# Booster_Board_20180904.net
KiCad netlist of a schematic drawn in Altium Designer
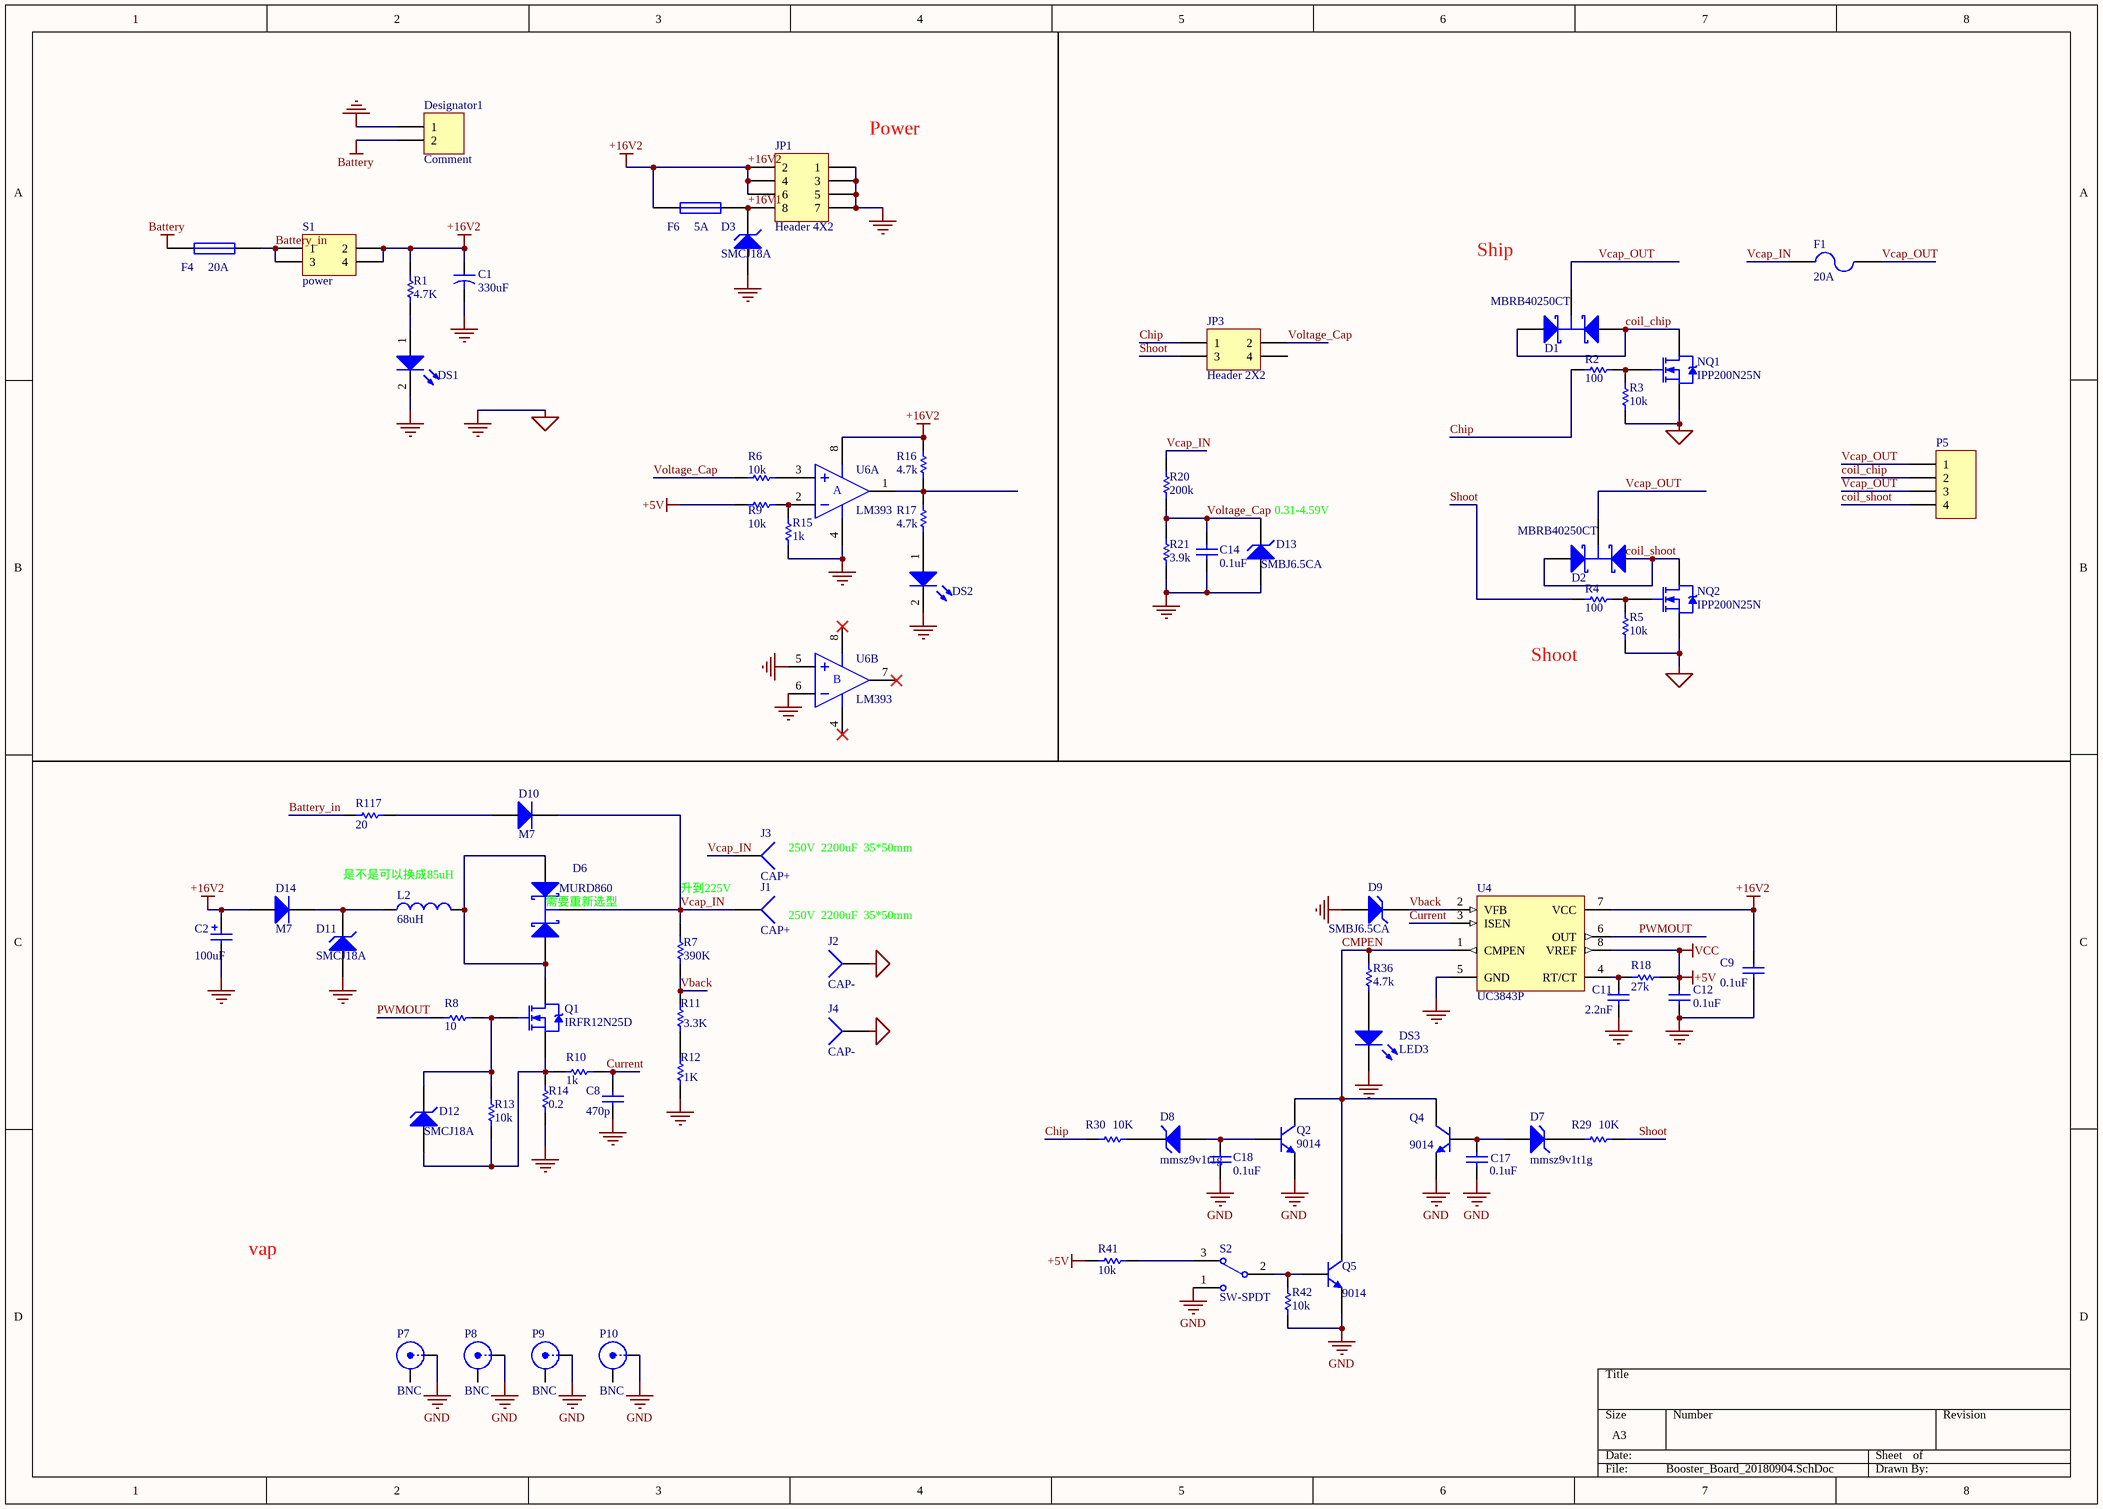
[diagram p0: Booster_Board_20180904.SchDoc]

(export (version "E")
  (design (tool "Eeschema 10.0.6"))
  (components
    (comp (ref "C1")
      (value "330uF")
      (footprint "J10")
      (description "Capacitor")
      (fields (field (name "PUBLISHER") "Altium Limited"))
      (libsource (lib "Miscellaneous Devices") (part "Cap2"))
    )
    (comp (ref "C2")
      (value "100uF")
      (footprint "J10")
      (description "Polarized Capacitor (Radial)")
      (fields
        (field (name "MANUFACTURER") "Generic Components")
        (field (name "Comment") "100uf")
        (field (name "PUBLISHER") "Altium Hobart Technology Centre")
      )
      (libsource (lib "Miscellaneous Devices") (part "Cap Pol1"))
    )
    (comp (ref "C8")
      (value "470p")
      (footprint "0805C")
      (description "Capacitor")
      (fields
        (field (name "MANUFACTURER") "Generic Components")
        (field (name "PUBLISHER") "Altium Hobart Technology Centre")
      )
      (libsource (lib "Miscellaneous Devices") (part "Cap"))
    )
    (comp (ref "C9")
      (value "0.1uF")
      (footprint "0805C")
      (description "Capacitor")
      (fields (field (name "PUBLISHER") "Altium Limited"))
      (libsource (lib "Miscellaneous Devices") (part "Cap"))
    )
    (comp (ref "C11")
      (value "2.2nF")
      (footprint "0805C")
      (description "Capacitor")
      (fields
        (field (name "MANUFACTURER") "Generic Components")
        (field (name "Comment") "2.2nf")
        (field (name "PUBLISHER") "Altium Hobart Technology Centre")
      )
      (libsource (lib "Miscellaneous Devices") (part "Cap"))
    )
    (comp (ref "C12")
      (value "0.1uF")
      (footprint "0805C")
      (description "Capacitor")
      (fields
        (field (name "MANUFACTURER") "Generic Components")
        (field (name "PUBLISHER") "Altium Hobart Technology Centre")
      )
      (libsource (lib "Miscellaneous Devices") (part "Cap"))
    )
    (comp (ref "C14")
      (value "0.1uF")
      (footprint "0805C")
      (description "Capacitor")
      (fields (field (name "PUBLISHER") "Altium Limited"))
      (libsource (lib "Miscellaneous Devices") (part "Cap"))
    )
    (comp (ref "C17")
      (value "0.1uF")
      (footprint "0805c")
      (description "Capacitor")
      (fields (field (name "PUBLISHER") "Altium Limited"))
      (libsource (lib "Miscellaneous Devices") (part "Cap"))
    )
    (comp (ref "C18")
      (value "0.1uF")
      (footprint "0805c")
      (description "Capacitor")
      (fields (field (name "PUBLISHER") "Altium Limited"))
      (libsource (lib "Miscellaneous Devices") (part "Cap"))
    )
    (comp (ref "D1")
      (value "MBRB40250CT")
      (footprint "D2PAK")
      (description "Schottky Rectifier")
      (fields
        (field (name "MANUFACTURER") "International Rectifier")
        (field (name "PUBLISHER") "Altium Hobart Technology Centre")
      )
      (libsource (lib "IR Discrete Diode") (part "MBRB1545CT"))
    )
    (comp (ref "D2")
      (value "MBRB40250CT")
      (footprint "D2PAK")
      (description "Schottky Rectifier")
      (fields
        (field (name "MANUFACTURER") "International Rectifier")
        (field (name "PUBLISHER") "Altium Hobart Technology Centre")
      )
      (libsource (lib "IR Discrete Diode") (part "MBRB1545CT"))
    )
    (comp (ref "D3")
      (value "SMCJ18A")
      (footprint "small_power_240:SMCJ18A")
      (description "Zener Diode")
      (fields (field (name "PUBLISHER") "Altium Limited"))
      (libsource (lib "Miscellaneous Devices") (part "D Zener"))
    )
    (comp (ref "D6")
      (value "MURD860")
      (footprint "DPAK")
      (description "Schottky Rectifier")
      (fields
        (field (name "MANUFACTURER") "International Rectifier")
        (field (name "PUBLISHER") "Altium Hobart Technology Centre")
      )
      (libsource (lib "IR Discrete Diode") (part "MBRB1545CT"))
    )
    (comp (ref "D7")
      (value "mmsz9v1t1g")
      (footprint "sod-123")
      (description "Zener Diode")
      (fields (field (name "PUBLISHER") "Altium Limited"))
      (libsource (lib "Miscellaneous Devices") (part "D Zener"))
    )
    (comp (ref "D8")
      (value "mmsz9v1t1g")
      (footprint "sod-123")
      (description "Zener Diode")
      (fields (field (name "PUBLISHER") "Altium Limited"))
      (libsource (lib "Miscellaneous Devices") (part "D Zener"))
    )
    (comp (ref "D9")
      (value "SMBJ6.5CA")
      (footprint "SMBJ6.5")
      (description "Zener Diode")
      (fields (field (name "PUBLISHER") "Altium Limited"))
      (libsource (lib "Miscellaneous Devices") (part "D Zener"))
    )
    (comp (ref "D10")
      (value "M7")
      (footprint "small_power_240:SMA")
      (description "Default Diode")
      (fields
        (field (name "MANUFACTURER") "Generic Components")
        (field (name "PUBLISHER") "Altium Hobart Technology Centre")
      )
      (libsource (lib "Miscellaneous Devices") (part "Diode"))
    )
    (comp (ref "D11")
      (value "SMCJ18A")
      (footprint "small_power_240:SMCJ18A")
      (description "Zener Diode")
      (fields (field (name "PUBLISHER") "Altium Limited"))
      (libsource (lib "Miscellaneous Devices") (part "D Zener"))
    )
    (comp (ref "D12")
      (value "SMCJ18A")
      (footprint "SMCJ18A")
      (description "Zener Diode")
      (fields (field (name "PUBLISHER") "Altium Limited"))
      (libsource (lib "Miscellaneous Devices") (part "D Zener"))
    )
    (comp (ref "D13")
      (value "SMBJ6.5CA")
      (footprint "SMBJ6.5")
      (description "Zener Diode")
      (fields (field (name "PUBLISHER") "Altium Limited"))
      (libsource (lib "Miscellaneous Devices") (part "D Zener"))
    )
    (comp (ref "D14")
      (value "M7")
      (footprint "small_power_240:SMA")
      (description "Default Diode")
      (fields
        (field (name "MANUFACTURER") "Generic Components")
        (field (name "PUBLISHER") "Altium Hobart Technology Centre")
      )
      (libsource (lib "Miscellaneous Devices") (part "Diode"))
    )
    (comp (ref "Designator1")
      (value "Comment")
      (footprint "XT60PW")
      (description "Header, 2-Pin")
      (fields (field (name "PUBLISHER") "Altium Limited"))
      (libsource (lib "Miscellaneous Connectors") (part "Header 2"))
    )
    (comp (ref "DS1")
      (value "LED2")
      (footprint "0805A")
      (description "Typical RED, GREEN, YELLOW, AMBER GaAs LED")
      (fields
        (field (name "MANUFACTURER") "Generic Components")
        (field (name "PUBLISHER") "Altium Hobart Technology Centre")
      )
      (libsource (lib "Miscellaneous Devices") (part "LED2"))
    )
    (comp (ref "DS2")
      (value "LED2")
      (footprint "0805A")
      (description "Typical RED, GREEN, YELLOW, AMBER GaAs LED")
      (fields
        (field (name "MANUFACTURER") "Generic Components")
        (field (name "PUBLISHER") "Altium Hobart Technology Centre")
      )
      (libsource (lib "Miscellaneous Devices") (part "LED2"))
    )
    (comp (ref "DS3")
      (value "LED3")
      (footprint "元器件:0805A")
      (description "Typical RED, GREEN, YELLOW, AMBER GaAs LED")
      (fields (field (name "PUBLISHER") "Altium Limited"))
      (libsource (lib "") (part "LED2_1"))
    )
    (comp (ref "F1")
      (value "20A")
      (footprint "20A")
      (fields (field (name "PUBLISHER") "Altium Limited"))
      (libsource (lib "Miscellaneous Devices") (part "Fuse 2"))
    )
    (comp (ref "F4")
      (value "20A")
      (footprint "20A")
      (description "Fuse")
      (fields (field (name "PUBLISHER") "Altium Limited"))
      (libsource (lib "Miscellaneous Devices") (part "Fuse 1"))
    )
    (comp (ref "F6")
      (value "5A")
      (footprint "3216F")
      (description "Fuse")
      (fields (field (name "PUBLISHER") "Altium Limited"))
      (libsource (lib "Miscellaneous Devices") (part "Fuse 1"))
    )
    (comp (ref "J1")
      (value "CAP+")
      (footprint "PIN1")
      (description "Socket")
      (fields (field (name "PUBLISHER") "Altium Limited"))
      (libsource (lib "Miscellaneous Connectors") (part "Socket"))
    )
    (comp (ref "J2")
      (value "CAP-")
      (footprint "PIN1")
      (description "Socket")
      (fields (field (name "PUBLISHER") "Altium Limited"))
      (libsource (lib "Miscellaneous Connectors") (part "Socket"))
    )
    (comp (ref "J3")
      (value "CAP+")
      (footprint "PIN1")
      (description "Socket")
      (fields (field (name "PUBLISHER") "Altium Limited"))
      (libsource (lib "Miscellaneous Connectors") (part "Socket"))
    )
    (comp (ref "J4")
      (value "CAP-")
      (footprint "pin1")
      (description "Socket")
      (fields (field (name "PUBLISHER") "Altium Limited"))
      (libsource (lib "Miscellaneous Connectors") (part "Socket"))
    )
    (comp (ref "JP1")
      (value "Header 4X2")
      (footprint "2*4_2.5mm")
      (description "Header, 4-Pin, Dual row")
      (fields (field (name "PUBLISHER") "Altium Limited"))
      (libsource (lib "Miscellaneous Connectors") (part "Header 4X2"))
    )
    (comp (ref "JP3")
      (value "Header 2X2")
      (footprint "2*2_2.5mm")
      (description "Header, 2-Pin, Dual row")
      (fields (field (name "PUBLISHER") "Altium Limited"))
      (libsource (lib "Miscellaneous Connectors") (part "Header 2X2"))
    )
    (comp (ref "L2")
      (value "68uH")
      (footprint "L2")
      (description "Inductor")
      (fields (field (name "PUBLISHER") "Altium Limited"))
      (libsource (lib "Miscellaneous Devices") (part "Inductor"))
    )
    (comp (ref "NQ1")
      (value "IPP200N25N")
      (footprint "TO-247")
      (description "HEXFET Power MOSFET")
      (fields
        (field (name "MANUFACTURER") "International Rectifier")
        (field (name "PUBLISHER") "Altium Hobart Technology Centre")
      )
      (libsource (lib "IR Discrete MOSFET") (part "IRFP460"))
    )
    (comp (ref "NQ2")
      (value "IPP200N25N")
      (footprint "TO-247")
      (description "HEXFET Power MOSFET")
      (fields
        (field (name "MANUFACTURER") "International Rectifier")
        (field (name "PUBLISHER") "Altium Hobart Technology Centre")
      )
      (libsource (lib "IR Discrete MOSFET") (part "IRFP460"))
    )
    (comp (ref "P5")
      (value "~")
      (footprint "ZJUNlict_footprint:CONNECTOR_CAP")
      (description "Header, 4-Pin")
      (fields (field (name "PUBLISHER") "Altium Limited"))
      (libsource (lib "Miscellaneous Connectors") (part "Header 4"))
    )
    (comp (ref "P7")
      (value "BNC")
      (footprint "hole")
      (description "BNC Elbow Connector")
      (fields (field (name "PUBLISHER") "Altium Limited"))
      (libsource (lib "Miscellaneous Connectors") (part "BNC"))
    )
    (comp (ref "P8")
      (value "BNC")
      (footprint "hole")
      (description "BNC Elbow Connector")
      (fields (field (name "PUBLISHER") "Altium Limited"))
      (libsource (lib "Miscellaneous Connectors") (part "BNC"))
    )
    (comp (ref "P9")
      (value "BNC")
      (footprint "hole")
      (description "BNC Elbow Connector")
      (fields (field (name "PUBLISHER") "Altium Limited"))
      (libsource (lib "Miscellaneous Connectors") (part "BNC"))
    )
    (comp (ref "P10")
      (value "BNC")
      (footprint "hole")
      (description "BNC Elbow Connector")
      (fields (field (name "PUBLISHER") "Altium Limited"))
      (libsource (lib "Miscellaneous Connectors") (part "BNC"))
    )
    (comp (ref "Q1")
      (value "IRFR12N25D")
      (footprint "DPAK")
      (description "N-Channel Power MOSFET")
      (fields (field (name "PUBLISHER") "Altium Limited"))
      (libsource (lib "Miscellaneous Devices") (part "NMOS-2"))
    )
    (comp (ref "Q2")
      (value "9014")
      (footprint "元器件:SOT23A")
      (description "NPN General Purpose Amplifier")
      (fields
        (field (name "MANUFACTURER") "Fairchild Semiconductor")
        (field (name "PUBLISHER") "Altium Hobart Technology Centre")
      )
      (libsource (lib "FSC Discrete BJT") (part "BC817-40"))
    )
    (comp (ref "Q4")
      (value "9014")
      (footprint "sot23a")
      (description "NPN General Purpose Amplifier")
      (fields
        (field (name "MANUFACTURER") "Fairchild Semiconductor")
        (field (name "PUBLISHER") "Altium Hobart Technology Centre")
      )
      (libsource (lib "FSC Discrete BJT") (part "BC817-40"))
    )
    (comp (ref "Q5")
      (value "9014")
      (footprint "SOT23a")
      (description "NPN General Purpose Amplifier")
      (fields
        (field (name "MANUFACTURER") "Fairchild Semiconductor")
        (field (name "PUBLISHER") "Altium Hobart Technology Centre")
      )
      (libsource (lib "FSC Discrete BJT") (part "BC817-40"))
    )
    (comp (ref "R1")
      (value "4.7K")
      (footprint "0805R")
      (description "Resistor")
      (fields
        (field (name "MANUFACTURER") "Generic Components")
        (field (name "Comment") "4.7k")
        (field (name "PUBLISHER") "Altium Hobart Technology Centre")
      )
      (libsource (lib "Miscellaneous Devices") (part "Res1"))
    )
    (comp (ref "R2")
      (value "100")
      (footprint "0805r")
      (description "Semiconductor Resistor")
      (fields
        (field (name "MANUFACTURER") "Generic Components")
        (field (name "PUBLISHER") "Altium Hobart Technology Centre")
      )
      (libsource (lib "Miscellaneous Devices") (part "Res Semi"))
    )
    (comp (ref "R3")
      (value "10k")
      (footprint "0805R")
      (description "Semiconductor Resistor")
      (fields
        (field (name "MANUFACTURER") "Generic Components")
        (field (name "PUBLISHER") "Altium Hobart Technology Centre")
      )
      (libsource (lib "Miscellaneous Devices") (part "Res Semi"))
    )
    (comp (ref "R4")
      (value "100")
      (footprint "0805r")
      (description "Semiconductor Resistor")
      (fields
        (field (name "MANUFACTURER") "Generic Components")
        (field (name "PUBLISHER") "Altium Hobart Technology Centre")
      )
      (libsource (lib "Miscellaneous Devices") (part "Res Semi"))
    )
    (comp (ref "R5")
      (value "10k")
      (footprint "0805R")
      (description "Semiconductor Resistor")
      (fields
        (field (name "MANUFACTURER") "Generic Components")
        (field (name "PUBLISHER") "Altium Hobart Technology Centre")
      )
      (libsource (lib "Miscellaneous Devices") (part "Res Semi"))
    )
    (comp (ref "R6")
      (value "10k")
      (footprint "0805R")
      (description "Resistor")
      (fields
        (field (name "MANUFACTURER") "Generic Components")
        (field (name "PUBLISHER") "Altium Hobart Technology Centre")
      )
      (libsource (lib "HAIBAO_MEGAV1.0_1") (part "Res1"))
    )
    (comp (ref "R7")
      (value "390K")
      (footprint "0805R")
      (description "Resistor")
      (fields
        (field (name "MANUFACTURER") "Generic Components")
        (field (name "PUBLISHER") "Altium Hobart Technology Centre")
      )
      (libsource (lib "Miscellaneous Devices") (part "Res1"))
    )
    (comp (ref "R8")
      (value "10")
      (footprint "0805R")
      (description "Resistor")
      (fields
        (field (name "MANUFACTURER") "Generic Components")
        (field (name "PUBLISHER") "Altium Hobart Technology Centre")
      )
      (libsource (lib "Miscellaneous Devices") (part "Res1"))
    )
    (comp (ref "R9")
      (value "10k")
      (footprint "0805R")
      (description "Resistor")
      (fields
        (field (name "MANUFACTURER") "Generic Components")
        (field (name "PUBLISHER") "Altium Hobart Technology Centre")
      )
      (libsource (lib "HAIBAO_MEGAV1.0_1") (part "Res1"))
    )
    (comp (ref "R10")
      (value "1k")
      (footprint "0805R")
      (description "Resistor")
      (fields
        (field (name "MANUFACTURER") "Generic Components")
        (field (name "PUBLISHER") "Altium Hobart Technology Centre")
      )
      (libsource (lib "Miscellaneous Devices") (part "Res1"))
    )
    (comp (ref "R11")
      (value "3.3K")
      (footprint "0805R")
      (description "Resistor")
      (fields
        (field (name "MANUFACTURER") "Generic Components")
        (field (name "PUBLISHER") "Altium Hobart Technology Centre")
      )
      (libsource (lib "Miscellaneous Devices") (part "Res1"))
    )
    (comp (ref "R12")
      (value "1K")
      (footprint "0805R")
      (description "Resistor")
      (fields
        (field (name "MANUFACTURER") "Generic Components")
        (field (name "PUBLISHER") "Altium Hobart Technology Centre")
      )
      (libsource (lib "Miscellaneous Devices") (part "Res1"))
    )
    (comp (ref "R13")
      (value "10k")
      (footprint "0805R")
      (description "Resistor")
      (fields
        (field (name "MANUFACTURER") "Generic Components")
        (field (name "PUBLISHER") "Altium Hobart Technology Centre")
      )
      (libsource (lib "Miscellaneous Devices") (part "Res1"))
    )
    (comp (ref "R14")
      (value "0.2")
      (footprint "0.2_4527R")
      (description "Resistor")
      (fields
        (field (name "MANUFACTURER") "Generic Components")
        (field (name "PUBLISHER") "Altium Hobart Technology Centre")
      )
      (libsource (lib "Miscellaneous Devices") (part "Res1"))
    )
    (comp (ref "R15")
      (value "1k")
      (footprint "0805R")
      (description "Resistor")
      (fields
        (field (name "MANUFACTURER") "Generic Components")
        (field (name "PUBLISHER") "Altium Hobart Technology Centre")
      )
      (libsource (lib "HAIBAO_MEGAV1.0_1") (part "Res1"))
    )
    (comp (ref "R16")
      (value "4.7k")
      (footprint "0805R")
      (description "Resistor")
      (fields
        (field (name "MANUFACTURER") "Generic Components")
        (field (name "PUBLISHER") "Altium Hobart Technology Centre")
      )
      (libsource (lib "HAIBAO_MEGAV1.0_1") (part "Res1"))
    )
    (comp (ref "R17")
      (value "4.7k")
      (footprint "0805R")
      (description "Resistor")
      (fields
        (field (name "MANUFACTURER") "Generic Components")
        (field (name "PUBLISHER") "Altium Hobart Technology Centre")
      )
      (libsource (lib "HAIBAO_MEGAV1.0_1") (part "Res1"))
    )
    (comp (ref "R18")
      (value "27k")
      (footprint "0805R")
      (description "Resistor")
      (fields
        (field (name "MANUFACTURER") "Generic Components")
        (field (name "PUBLISHER") "Altium Hobart Technology Centre")
      )
      (libsource (lib "Miscellaneous Devices") (part "Res1"))
    )
    (comp (ref "R20")
      (value "200k")
      (footprint "0805R")
      (description "Resistor")
      (fields
        (field (name "MANUFACTURER") "Generic Components")
        (field (name "PUBLISHER") "Altium Hobart Technology Centre")
      )
      (libsource (lib "Miscellaneous Devices") (part "Res1"))
    )
    (comp (ref "R21")
      (value "3.9k")
      (footprint "0805R")
      (description "Resistor")
      (fields
        (field (name "MANUFACTURER") "Generic Components")
        (field (name "PUBLISHER") "Altium Hobart Technology Centre")
      )
      (libsource (lib "Miscellaneous Devices") (part "Res1"))
    )
    (comp (ref "R29")
      (value "10K")
      (footprint "0805r")
      (description "Resistor")
      (fields
        (field (name "MANUFACTURER") "Generic Components")
        (field (name "Comment") "10k")
        (field (name "PUBLISHER") "Altium Hobart Technology Centre")
      )
      (libsource (lib "Miscellaneous Devices") (part "Res1"))
    )
    (comp (ref "R30")
      (value "10K")
      (footprint "0805r")
      (description "Resistor")
      (fields
        (field (name "MANUFACTURER") "Generic Components")
        (field (name "Comment") "10k")
        (field (name "PUBLISHER") "Altium Hobart Technology Centre")
      )
      (libsource (lib "Miscellaneous Devices") (part "Res1"))
    )
    (comp (ref "R36")
      (value "4.7k")
      (footprint "0805r")
      (description "Resistor")
      (fields
        (field (name "MANUFACTURER") "Generic Components")
        (field (name "PUBLISHER") "Altium Hobart Technology Centre")
      )
      (libsource (lib "Miscellaneous Devices") (part "Res1"))
    )
    (comp (ref "R41")
      (value "10k")
      (footprint "0805r")
      (description "Resistor")
      (fields
        (field (name "MANUFACTURER") "Generic Components")
        (field (name "PUBLISHER") "Altium Hobart Technology Centre")
      )
      (libsource (lib "Miscellaneous Devices") (part "Res1"))
    )
    (comp (ref "R42")
      (value "10k")
      (footprint "0805r")
      (description "Resistor")
      (fields
        (field (name "MANUFACTURER") "Generic Components")
        (field (name "PUBLISHER") "Altium Hobart Technology Centre")
      )
      (libsource (lib "Miscellaneous Devices") (part "Res1"))
    )
    (comp (ref "R117")
      (value "20")
      (footprint "20_2512r")
      (description "Resistor")
      (fields
        (field (name "MANUFACTURER") "Generic Components")
        (field (name "PUBLISHER") "Altium Hobart Technology Centre")
      )
      (libsource (lib "Miscellaneous Devices") (part "Res1"))
    )
    (comp (ref "S1")
      (value "power")
      (footprint "Rocker_Switch")
      (description "Header, 2-Pin, Dual row")
      (fields (field (name "PUBLISHER") "Altium Limited"))
      (libsource (lib "Miscellaneous Connectors") (part "Header 2X2"))
    )
    (comp (ref "S2")
      (value "SW-SPDT")
      (footprint "卧式开关-2")
      (description "SPDT Subminiature Toggle Switch, Right Angle Mounting, Vertical Actuation")
      (fields (field (name "PUBLISHER") "Altium Limited"))
      (libsource (lib "Miscellaneous Devices") (part "SW-SPDT"))
    )
    (comp (ref "U4")
      (value "UC3843P")
      (footprint "SO-G8")
      (description "Current-Mode PWM Controller")
      (fields (field (name "PUBLISHER") "Altium Limited"))
      (libsource (lib "TI Power Mgt DC-DC Converter") (part "UC3843P"))
    )
    (comp (ref "U6")
      (value "LM393")
      (footprint "LM393_SO-G8")
      (libsource (lib "HAIBAO_MEGAV1.0_1") (part "LM393"))
    )
  )
  (nets
    (net (code "1") (name "+5V") (class "Default")
      (node (ref "C12") (pin "1") (pinfunction "1_1") (pintype "passive"))
      (node (ref "R18") (pin "2") (pinfunction "2_2") (pintype "passive"))
      (node (ref "R41") (pin "2") (pinfunction "2_2") (pintype "passive"))
      (node (ref "R9") (pin "2") (pinfunction "2_2") (pintype "passive"))
      (node (ref "U4") (pin "8") (pinfunction "VREF_8") (pintype "output"))
    )
    (net (code "2") (name "+16V2") (class "Default")
      (node (ref "C1") (pin "1") (pinfunction "1_1") (pintype "passive"))
      (node (ref "C2") (pin "1") (pinfunction "1_1") (pintype "passive"))
      (node (ref "C9") (pin "2") (pinfunction "2_2") (pintype "passive"))
      (node (ref "D14") (pin "1") (pinfunction "A_1") (pintype "passive"))
      (node (ref "F6") (pin "2") (pinfunction "2_2") (pintype "passive"))
      (node (ref "JP1") (pin "2") (pinfunction "2_2") (pintype "passive"))
      (node (ref "JP1") (pin "4") (pinfunction "4_4") (pintype "passive"))
      (node (ref "JP1") (pin "6") (pinfunction "6_6") (pintype "passive"))
      (node (ref "R1") (pin "2") (pinfunction "2_2") (pintype "passive"))
      (node (ref "R16") (pin "2") (pinfunction "2_2") (pintype "passive"))
      (node (ref "S1") (pin "2") (pinfunction "2_2") (pintype "passive"))
      (node (ref "S1") (pin "4") (pinfunction "4_4") (pintype "passive"))
      (node (ref "U4") (pin "7") (pinfunction "VCC_7") (pintype "power_in"))
      (node (ref "U6") (pin "8") (pinfunction "V+_8") (pintype "power_in"))
    )
    (net (code "3") (name "/+16V1") (class "Default")
      (node (ref "D3") (pin "2") (pinfunction "K_2") (pintype "passive"))
      (node (ref "F6") (pin "1") (pinfunction "1_1") (pintype "passive"))
      (node (ref "JP1") (pin "8") (pinfunction "8_8") (pintype "passive"))
    )
    (net (code "4") (name "/Battery_in") (class "Default")
      (node (ref "F4") (pin "1") (pinfunction "1_1") (pintype "passive"))
      (node (ref "R117") (pin "2") (pinfunction "2_2") (pintype "passive"))
      (node (ref "S1") (pin "1") (pinfunction "1_1") (pintype "passive"))
      (node (ref "S1") (pin "3") (pinfunction "3_3") (pintype "passive"))
    )
    (net (code "5") (name "/CMPEN") (class "Default")
      (node (ref "Q2") (pin "3") (pinfunction "C_3") (pintype "passive"))
      (node (ref "Q4") (pin "3") (pinfunction "C_3") (pintype "passive"))
      (node (ref "Q5") (pin "3") (pinfunction "C_3") (pintype "passive"))
      (node (ref "R36") (pin "2") (pinfunction "2_2") (pintype "passive"))
      (node (ref "U4") (pin "1") (pinfunction "CMPEN_1") (pintype "output"))
    )
    (net (code "6") (name "/Chip") (class "Default")
      (node (ref "JP3") (pin "1") (pinfunction "1_1") (pintype "passive"))
      (node (ref "R2") (pin "1") (pinfunction "1_1") (pintype "passive"))
      (node (ref "R30") (pin "1") (pinfunction "1_1") (pintype "passive"))
    )
    (net (code "7") (name "/Current") (class "Default")
      (node (ref "C8") (pin "1") (pinfunction "1_1") (pintype "passive"))
      (node (ref "R10") (pin "2") (pinfunction "2_2") (pintype "passive"))
      (node (ref "U4") (pin "3") (pinfunction "ISEN_3") (pintype "input"))
    )
    (net (code "8") (name "/PWMOUT") (class "Default")
      (node (ref "R8") (pin "1") (pinfunction "1_1") (pintype "passive"))
      (node (ref "U4") (pin "6") (pinfunction "OUT_6") (pintype "output"))
    )
    (net (code "9") (name "/Shoot") (class "Default")
      (node (ref "JP3") (pin "3") (pinfunction "3_3") (pintype "passive"))
      (node (ref "R29") (pin "2") (pinfunction "2_2") (pintype "passive"))
      (node (ref "R4") (pin "1") (pinfunction "1_1") (pintype "passive"))
    )
    (net (code "10") (name "/Vback") (class "Default")
      (node (ref "D9") (pin "2") (pinfunction "K_2") (pintype "passive"))
      (node (ref "R11") (pin "2") (pinfunction "2_2") (pintype "passive"))
      (node (ref "R7") (pin "1") (pinfunction "1_1") (pintype "passive"))
      (node (ref "U4") (pin "2") (pinfunction "VFB_2") (pintype "input"))
    )
    (net (code "11") (name "/Vcap_IN") (class "Default")
      (node (ref "D10") (pin "2") (pinfunction "K_2") (pintype "passive"))
      (node (ref "D6") (pin "2") (pinfunction "K_2") (pintype "passive"))
      (node (ref "F1") (pin "1") (pinfunction "1_1") (pintype "passive"))
      (node (ref "J1") (pin "1") (pinfunction "1_1") (pintype "passive"))
      (node (ref "J3") (pin "1") (pinfunction "1_1") (pintype "passive"))
      (node (ref "R20") (pin "2") (pinfunction "2_2") (pintype "passive"))
      (node (ref "R7") (pin "2") (pinfunction "2_2") (pintype "passive"))
    )
    (net (code "12") (name "/Vcap_OUT") (class "Default")
      (node (ref "D1") (pin "2") (pinfunction "K_2") (pintype "passive"))
      (node (ref "D2") (pin "2") (pinfunction "K_2") (pintype "passive"))
      (node (ref "F1") (pin "2") (pinfunction "2_2") (pintype "passive"))
      (node (ref "P5") (pin "1") (pinfunction "1_1") (pintype "passive"))
      (node (ref "P5") (pin "3") (pinfunction "3_3") (pintype "passive"))
    )
    (net (code "13") (name "/Voltage_Cap") (class "Default")
      (node (ref "C14") (pin "2") (pinfunction "2_2") (pintype "passive"))
      (node (ref "D13") (pin "2") (pinfunction "K_2") (pintype "passive"))
      (node (ref "JP3") (pin "2") (pinfunction "2_2") (pintype "passive"))
      (node (ref "R20") (pin "1") (pinfunction "1_1") (pintype "passive"))
      (node (ref "R21") (pin "2") (pinfunction "2_2") (pintype "passive"))
      (node (ref "R6") (pin "2") (pinfunction "2_2") (pintype "passive"))
    )
    (net (code "14") (name "/coil_chip") (class "Default")
      (node (ref "D1") (pin "1") (pinfunction "A1_1") (pintype "passive"))
      (node (ref "D1") (pin "3") (pinfunction "A2_3") (pintype "passive"))
      (node (ref "NQ1") (pin "2") (pinfunction "D_2") (pintype "passive"))
      (node (ref "P5") (pin "2") (pinfunction "2_2") (pintype "passive"))
    )
    (net (code "15") (name "/coil_shoot") (class "Default")
      (node (ref "D2") (pin "1") (pinfunction "A1_1") (pintype "passive"))
      (node (ref "D2") (pin "3") (pinfunction "A2_3") (pintype "passive"))
      (node (ref "NQ2") (pin "2") (pinfunction "D_2") (pintype "passive"))
      (node (ref "P5") (pin "4") (pinfunction "4_4") (pintype "passive"))
    )
    (net (code "16") (name "Battery") (class "Default")
      (node (ref "Designator1") (pin "2") (pinfunction "2_2") (pintype "passive"))
      (node (ref "F4") (pin "2") (pinfunction "2_2") (pintype "passive"))
    )
    (net (code "17") (name "GND") (class "Default")
      (node (ref "C1") (pin "2") (pinfunction "2_2") (pintype "passive"))
      (node (ref "C11") (pin "2") (pinfunction "2_2") (pintype "passive"))
      (node (ref "C12") (pin "2") (pinfunction "2_2") (pintype "passive"))
      (node (ref "C14") (pin "1") (pinfunction "1_1") (pintype "passive"))
      (node (ref "C17") (pin "1") (pinfunction "1_1") (pintype "passive"))
      (node (ref "C18") (pin "1") (pinfunction "1_1") (pintype "passive"))
      (node (ref "C2") (pin "2") (pinfunction "2_2") (pintype "passive"))
      (node (ref "C8") (pin "2") (pinfunction "2_2") (pintype "passive"))
      (node (ref "C9") (pin "1") (pinfunction "1_1") (pintype "passive"))
      (node (ref "D11") (pin "1") (pinfunction "A_1") (pintype "passive"))
      (node (ref "D13") (pin "1") (pinfunction "A_1") (pintype "passive"))
      (node (ref "D3") (pin "1") (pinfunction "A_1") (pintype "passive"))
      (node (ref "D9") (pin "1") (pinfunction "A_1") (pintype "passive"))
      (node (ref "DS1") (pin "2") (pinfunction "K_2") (pintype "passive"))
      (node (ref "DS2") (pin "2") (pinfunction "K_2") (pintype "passive"))
      (node (ref "DS3") (pin "2") (pinfunction "K_2") (pintype "passive"))
      (node (ref "Designator1") (pin "1") (pinfunction "1_1") (pintype "passive"))
      (node (ref "J2") (pin "1") (pinfunction "1_1") (pintype "passive"))
      (node (ref "J4") (pin "1") (pinfunction "1_1") (pintype "passive"))
      (node (ref "JP1") (pin "1") (pinfunction "1_1") (pintype "passive"))
      (node (ref "JP1") (pin "3") (pinfunction "3_3") (pintype "passive"))
      (node (ref "JP1") (pin "5") (pinfunction "5_5") (pintype "passive"))
      (node (ref "JP1") (pin "7") (pinfunction "7_7") (pintype "passive"))
      (node (ref "NQ1") (pin "3") (pinfunction "S_3") (pintype "passive"))
      (node (ref "NQ2") (pin "3") (pinfunction "S_3") (pintype "passive"))
      (node (ref "P10") (pin "1") (pinfunction "X_1") (pintype "passive"))
      (node (ref "P7") (pin "1") (pinfunction "X_1") (pintype "passive"))
      (node (ref "P8") (pin "1") (pinfunction "X_1") (pintype "passive"))
      (node (ref "P9") (pin "1") (pinfunction "X_1") (pintype "passive"))
      (node (ref "Q2") (pin "2") (pinfunction "E_2") (pintype "passive"))
      (node (ref "Q4") (pin "2") (pinfunction "E_2") (pintype "passive"))
      (node (ref "Q5") (pin "2") (pinfunction "E_2") (pintype "passive"))
      (node (ref "R12") (pin "1") (pinfunction "1_1") (pintype "passive"))
      (node (ref "R14") (pin "1") (pinfunction "1_1") (pintype "passive"))
      (node (ref "R15") (pin "2") (pinfunction "2_2") (pintype "passive"))
      (node (ref "R21") (pin "1") (pinfunction "1_1") (pintype "passive"))
      (node (ref "R3") (pin "1") (pinfunction "1_1") (pintype "passive"))
      (node (ref "R42") (pin "2") (pinfunction "2_2") (pintype "passive"))
      (node (ref "R5") (pin "1") (pinfunction "1_1") (pintype "passive"))
      (node (ref "S2") (pin "1") (pinfunction "1_1") (pintype "passive"))
      (node (ref "U4") (pin "5") (pinfunction "GND_5") (pintype "power_in"))
      (node (ref "U6") (pin "4") (pinfunction "V-_4") (pintype "power_in"))
      (node (ref "U6") (pin "5") (pinfunction "IN+_5") (pintype "power_in"))
      (node (ref "U6") (pin "6") (pinfunction "IN-_6") (pintype "power_in"))
    )
    (net (code "18") (name "Net-(D6-A1)") (class "Default")
      (node (ref "D6") (pin "1") (pinfunction "A1_1") (pintype "passive"))
      (node (ref "D6") (pin "3") (pinfunction "A2_3") (pintype "passive"))
      (node (ref "L2") (pin "2") (pinfunction "2_2") (pintype "passive"))
      (node (ref "Q1") (pin "2") (pinfunction "D_2") (pintype "passive"))
    )
    (net (code "19") (name "Net-(D7-A)") (class "Default")
      (node (ref "C17") (pin "2") (pinfunction "2_2") (pintype "passive"))
      (node (ref "D7") (pin "1") (pinfunction "A_1") (pintype "passive"))
      (node (ref "Q4") (pin "1") (pinfunction "B_1") (pintype "passive"))
    )
    (net (code "20") (name "Net-(D7-K)") (class "Default")
      (node (ref "D7") (pin "2") (pinfunction "K_2") (pintype "passive"))
      (node (ref "R29") (pin "1") (pinfunction "1_1") (pintype "passive"))
    )
    (net (code "21") (name "Net-(D8-A)") (class "Default")
      (node (ref "C18") (pin "2") (pinfunction "2_2") (pintype "passive"))
      (node (ref "D8") (pin "1") (pinfunction "A_1") (pintype "passive"))
      (node (ref "Q2") (pin "1") (pinfunction "B_1") (pintype "passive"))
    )
    (net (code "22") (name "Net-(D8-K)") (class "Default")
      (node (ref "D8") (pin "2") (pinfunction "K_2") (pintype "passive"))
      (node (ref "R30") (pin "2") (pinfunction "2_2") (pintype "passive"))
    )
    (net (code "23") (name "Net-(D10-A)") (class "Default")
      (node (ref "D10") (pin "1") (pinfunction "A_1") (pintype "passive"))
      (node (ref "R117") (pin "1") (pinfunction "1_1") (pintype "passive"))
    )
    (net (code "24") (name "Net-(D11-K)") (class "Default")
      (node (ref "D11") (pin "2") (pinfunction "K_2") (pintype "passive"))
      (node (ref "D14") (pin "2") (pinfunction "K_2") (pintype "passive"))
      (node (ref "L2") (pin "1") (pinfunction "1_1") (pintype "passive"))
    )
    (net (code "25") (name "Net-(D12-A)") (class "Default")
      (node (ref "D12") (pin "1") (pinfunction "A_1") (pintype "passive"))
      (node (ref "Q1") (pin "3") (pinfunction "S_3") (pintype "passive"))
      (node (ref "R10") (pin "1") (pinfunction "1_1") (pintype "passive"))
      (node (ref "R13") (pin "1") (pinfunction "1_1") (pintype "passive"))
      (node (ref "R14") (pin "2") (pinfunction "2_2") (pintype "passive"))
    )
    (net (code "26") (name "Net-(D12-K)") (class "Default")
      (node (ref "D12") (pin "2") (pinfunction "K_2") (pintype "passive"))
      (node (ref "Q1") (pin "1") (pinfunction "G_1") (pintype "passive"))
      (node (ref "R13") (pin "2") (pinfunction "2_2") (pintype "passive"))
      (node (ref "R8") (pin "2") (pinfunction "2_2") (pintype "passive"))
    )
    (net (code "27") (name "Net-(DS1-A)") (class "Default")
      (node (ref "DS1") (pin "1") (pinfunction "A_1") (pintype "passive"))
      (node (ref "R1") (pin "1") (pinfunction "1_1") (pintype "passive"))
    )
    (net (code "28") (name "Net-(DS2-A)") (class "Default")
      (node (ref "DS2") (pin "1") (pinfunction "A_1") (pintype "passive"))
      (node (ref "R17") (pin "1") (pinfunction "1_1") (pintype "passive"))
    )
    (net (code "29") (name "Net-(DS3-A)") (class "Default")
      (node (ref "DS3") (pin "1") (pinfunction "A_1") (pintype "passive"))
      (node (ref "R36") (pin "1") (pinfunction "1_1") (pintype "passive"))
    )
    (net (code "30") (name "Net-(NQ1-G)") (class "Default")
      (node (ref "NQ1") (pin "1") (pinfunction "G_1") (pintype "passive"))
      (node (ref "R2") (pin "2") (pinfunction "2_2") (pintype "passive"))
      (node (ref "R3") (pin "2") (pinfunction "2_2") (pintype "passive"))
    )
    (net (code "31") (name "Net-(NQ2-G)") (class "Default")
      (node (ref "NQ2") (pin "1") (pinfunction "G_1") (pintype "passive"))
      (node (ref "R4") (pin "2") (pinfunction "2_2") (pintype "passive"))
      (node (ref "R5") (pin "2") (pinfunction "2_2") (pintype "passive"))
    )
    (net (code "32") (name "Net-(Q5-B)") (class "Default")
      (node (ref "Q5") (pin "1") (pinfunction "B_1") (pintype "passive"))
      (node (ref "R42") (pin "1") (pinfunction "1_1") (pintype "passive"))
      (node (ref "S2") (pin "2") (pinfunction "2_2") (pintype "passive"))
    )
    (net (code "33") (name "Net-(R11-Pad1)") (class "Default")
      (node (ref "R11") (pin "1") (pinfunction "1_1") (pintype "passive"))
      (node (ref "R12") (pin "2") (pinfunction "2_2") (pintype "passive"))
    )
    (net (code "34") (name "Net-(R41-Pad1)") (class "Default")
      (node (ref "R41") (pin "1") (pinfunction "1_1") (pintype "passive"))
      (node (ref "S2") (pin "3") (pinfunction "3_3") (pintype "passive"))
    )
    (net (code "35") (name "Net-(U4-RT{slash}CT)") (class "Default")
      (node (ref "C11") (pin "1") (pinfunction "1_1") (pintype "passive"))
      (node (ref "R18") (pin "1") (pinfunction "1_1") (pintype "passive"))
      (node (ref "U4") (pin "4") (pinfunction "RT/CT_4") (pintype "passive"))
    )
    (net (code "36") (name "Net-(U6A-IN+)") (class "Default")
      (node (ref "R6") (pin "1") (pinfunction "1_1") (pintype "passive"))
      (node (ref "U6") (pin "3") (pinfunction "IN+_3") (pintype "power_in"))
    )
    (net (code "37") (name "Net-(U6A-IN-)") (class "Default")
      (node (ref "R15") (pin "1") (pinfunction "1_1") (pintype "passive"))
      (node (ref "R9") (pin "1") (pinfunction "1_1") (pintype "passive"))
      (node (ref "U6") (pin "2") (pinfunction "IN-_2") (pintype "power_in"))
    )
    (net (code "38") (name "Net-(U6A-OUT)") (class "Default")
      (node (ref "R16") (pin "1") (pinfunction "1_1") (pintype "passive"))
      (node (ref "R17") (pin "2") (pinfunction "2_2") (pintype "passive"))
      (node (ref "U6") (pin "1") (pinfunction "OUT_1") (pintype "power_in"))
    )
    (net (code "39") (name "unconnected-(JP3-Pad4)") (class "Default")
      (node (ref "JP3") (pin "4") (pinfunction "4_4") (pintype "passive"))
    )
    (net (code "40") (name "unconnected-(P7-Y-Pad2)") (class "Default")
      (node (ref "P7") (pin "2") (pinfunction "Y_2") (pintype "passive"))
    )
    (net (code "41") (name "unconnected-(P8-Y-Pad2)") (class "Default")
      (node (ref "P8") (pin "2") (pinfunction "Y_2") (pintype "passive"))
    )
    (net (code "42") (name "unconnected-(P9-Y-Pad2)") (class "Default")
      (node (ref "P9") (pin "2") (pinfunction "Y_2") (pintype "passive"))
    )
    (net (code "43") (name "unconnected-(P10-Y-Pad2)") (class "Default")
      (node (ref "P10") (pin "2") (pinfunction "Y_2") (pintype "passive"))
    )
    (net (code "44") (name "unconnected-(U6B-OUT-Pad7)") (class "Default")
      (node (ref "U6") (pin "7") (pinfunction "OUT_7") (pintype "power_in+no_connect"))
    )
    (net (code "45") (name "unconnected-(U6B-V+-Pad8)") (class "Default")
      (node (ref "U6") (pin "8") (pinfunction "V+_8") (pintype "power_in+no_connect"))
    )
    (net (code "46") (name "unconnected-(U6B-V--Pad4)") (class "Default")
      (node (ref "U6") (pin "4") (pinfunction "V-_4") (pintype "power_in+no_connect"))
    )
  )
)
